# photocell_mk2.net
KiCad netlist of a schematic drawn in EAGLE
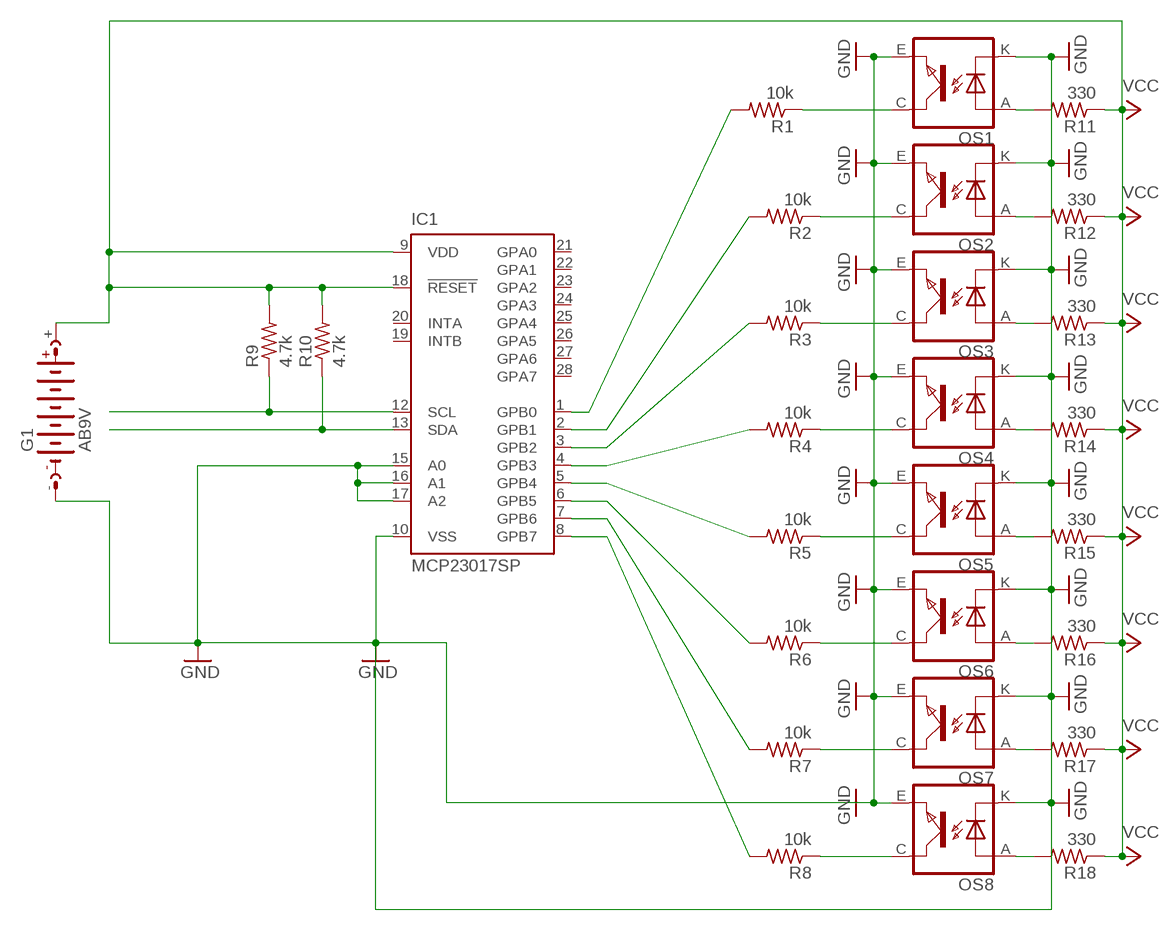
[diagram p0: schematic, sheet 1]

(export (version "E")
  (design (tool "Eeschema 10.0.6"))
  (components
    (comp (ref "G1")
      (value "AB9V")
      (footprint "eagle-import:AB9V")
      (libsource (lib "eagle-import") (part "AB9V"))
    )
    (comp (ref "IC1")
      (value "MCP23017SP")
      (footprint "eagle-import:DIL28-3")
      (fields (field (name "MF") "MICROCHIP") (field (name "MPN") "MCP23017-E/SP"))
      (libsource (lib "eagle-import") (part "MCP23017SP"))
    )
    (comp (ref "OS1")
      (value "TCRT5000")
      (footprint "eagle-import:TCRT5000")
      (libsource (lib "eagle-import") (part "TCRT5000"))
    )
    (comp (ref "OS2")
      (value "TCRT5000")
      (footprint "eagle-import:TCRT5000")
      (libsource (lib "eagle-import") (part "TCRT5000"))
    )
    (comp (ref "OS3")
      (value "TCRT5000")
      (footprint "eagle-import:TCRT5000")
      (libsource (lib "eagle-import") (part "TCRT5000"))
    )
    (comp (ref "OS4")
      (value "TCRT5000")
      (footprint "eagle-import:TCRT5000")
      (libsource (lib "eagle-import") (part "TCRT5000"))
    )
    (comp (ref "OS5")
      (value "TCRT5000")
      (footprint "eagle-import:TCRT5000")
      (libsource (lib "eagle-import") (part "TCRT5000"))
    )
    (comp (ref "OS6")
      (value "TCRT5000")
      (footprint "eagle-import:TCRT5000")
      (libsource (lib "eagle-import") (part "TCRT5000"))
    )
    (comp (ref "OS7")
      (value "TCRT5000")
      (footprint "eagle-import:TCRT5000")
      (libsource (lib "eagle-import") (part "TCRT5000"))
    )
    (comp (ref "OS8")
      (value "TCRT5000")
      (footprint "eagle-import:TCRT5000")
      (libsource (lib "eagle-import") (part "TCRT5000"))
    )
    (comp (ref "R1")
      (value "10k")
      (footprint "eagle-import:0204_7")
      (libsource (lib "eagle-import") (part "R-US_0204/7"))
    )
    (comp (ref "R2")
      (value "10k")
      (footprint "eagle-import:0204_7")
      (libsource (lib "eagle-import") (part "R-US_0204/7"))
    )
    (comp (ref "R3")
      (value "10k")
      (footprint "eagle-import:0204_7")
      (libsource (lib "eagle-import") (part "R-US_0204/7"))
    )
    (comp (ref "R4")
      (value "10k")
      (footprint "eagle-import:0204_7")
      (libsource (lib "eagle-import") (part "R-US_0204/7"))
    )
    (comp (ref "R5")
      (value "10k")
      (footprint "eagle-import:0204_7")
      (libsource (lib "eagle-import") (part "R-US_0204/7"))
    )
    (comp (ref "R6")
      (value "10k")
      (footprint "eagle-import:0204_7")
      (libsource (lib "eagle-import") (part "R-US_0204/7"))
    )
    (comp (ref "R7")
      (value "10k")
      (footprint "eagle-import:0204_7")
      (libsource (lib "eagle-import") (part "R-US_0204/7"))
    )
    (comp (ref "R8")
      (value "10k")
      (footprint "eagle-import:0204_7")
      (libsource (lib "eagle-import") (part "R-US_0204/7"))
    )
    (comp (ref "R9")
      (value "4.7k")
      (footprint "eagle-import:0204_7")
      (libsource (lib "eagle-import") (part "R-US_0204/7"))
    )
    (comp (ref "R10")
      (value "4.7k")
      (footprint "eagle-import:0204_7")
      (libsource (lib "eagle-import") (part "R-US_0204/7"))
    )
    (comp (ref "R11")
      (value "330")
      (footprint "eagle-import:0204_7")
      (libsource (lib "eagle-import") (part "R-US_0204/7"))
    )
    (comp (ref "R12")
      (value "330")
      (footprint "eagle-import:0204_7")
      (libsource (lib "eagle-import") (part "R-US_0204/7"))
    )
    (comp (ref "R13")
      (value "330")
      (footprint "eagle-import:0204_7")
      (libsource (lib "eagle-import") (part "R-US_0204/7"))
    )
    (comp (ref "R14")
      (value "330")
      (footprint "eagle-import:0204_7")
      (libsource (lib "eagle-import") (part "R-US_0204/7"))
    )
    (comp (ref "R15")
      (value "330")
      (footprint "eagle-import:0204_7")
      (libsource (lib "eagle-import") (part "R-US_0204/7"))
    )
    (comp (ref "R16")
      (value "330")
      (footprint "eagle-import:0204_7")
      (libsource (lib "eagle-import") (part "R-US_0204/7"))
    )
    (comp (ref "R17")
      (value "330")
      (footprint "eagle-import:0204_7")
      (libsource (lib "eagle-import") (part "R-US_0204/7"))
    )
    (comp (ref "R18")
      (value "330")
      (footprint "eagle-import:0204_7")
      (libsource (lib "eagle-import") (part "R-US_0204/7"))
    )
  )
  (nets
    (net (code "1") (name "GND") (class "Default")
      (node (ref "G1") (pin "-") (pinfunction "-_-") (pintype "passive"))
      (node (ref "IC1") (pin "10") (pinfunction "VSS_10") (pintype "power_in"))
      (node (ref "IC1") (pin "15") (pinfunction "A0_15") (pintype "input"))
      (node (ref "IC1") (pin "16") (pinfunction "A1_16") (pintype "input"))
      (node (ref "IC1") (pin "17") (pinfunction "A2_17") (pintype "input"))
      (node (ref "OS1") (pin "E") (pinfunction "EMITTER_E") (pintype "passive"))
      (node (ref "OS1") (pin "K") (pinfunction "CATHODE_K") (pintype "passive"))
      (node (ref "OS2") (pin "E") (pinfunction "EMITTER_E") (pintype "passive"))
      (node (ref "OS2") (pin "K") (pinfunction "CATHODE_K") (pintype "passive"))
      (node (ref "OS3") (pin "E") (pinfunction "EMITTER_E") (pintype "passive"))
      (node (ref "OS3") (pin "K") (pinfunction "CATHODE_K") (pintype "passive"))
      (node (ref "OS4") (pin "E") (pinfunction "EMITTER_E") (pintype "passive"))
      (node (ref "OS4") (pin "K") (pinfunction "CATHODE_K") (pintype "passive"))
      (node (ref "OS5") (pin "E") (pinfunction "EMITTER_E") (pintype "passive"))
      (node (ref "OS5") (pin "K") (pinfunction "CATHODE_K") (pintype "passive"))
      (node (ref "OS6") (pin "E") (pinfunction "EMITTER_E") (pintype "passive"))
      (node (ref "OS6") (pin "K") (pinfunction "CATHODE_K") (pintype "passive"))
      (node (ref "OS7") (pin "E") (pinfunction "EMITTER_E") (pintype "passive"))
      (node (ref "OS7") (pin "K") (pinfunction "CATHODE_K") (pintype "passive"))
      (node (ref "OS8") (pin "E") (pinfunction "EMITTER_E") (pintype "passive"))
      (node (ref "OS8") (pin "K") (pinfunction "CATHODE_K") (pintype "passive"))
    )
    (net (code "2") (name "Net-(IC1-GPB0)") (class "Default")
      (node (ref "IC1") (pin "1") (pinfunction "GPB0_1") (pintype "bidirectional"))
      (node (ref "R1") (pin "2") (pinfunction "2_2") (pintype "passive"))
    )
    (net (code "3") (name "Net-(IC1-GPB1)") (class "Default")
      (node (ref "IC1") (pin "2") (pinfunction "GPB1_2") (pintype "bidirectional"))
      (node (ref "R2") (pin "2") (pinfunction "2_2") (pintype "passive"))
    )
    (net (code "4") (name "Net-(IC1-GPB2)") (class "Default")
      (node (ref "IC1") (pin "3") (pinfunction "GPB2_3") (pintype "bidirectional"))
      (node (ref "R3") (pin "2") (pinfunction "2_2") (pintype "passive"))
    )
    (net (code "5") (name "Net-(IC1-GPB3)") (class "Default")
      (node (ref "IC1") (pin "4") (pinfunction "GPB3_4") (pintype "bidirectional"))
      (node (ref "R4") (pin "2") (pinfunction "2_2") (pintype "passive"))
    )
    (net (code "6") (name "Net-(IC1-GPB4)") (class "Default")
      (node (ref "IC1") (pin "5") (pinfunction "GPB4_5") (pintype "bidirectional"))
      (node (ref "R5") (pin "2") (pinfunction "2_2") (pintype "passive"))
    )
    (net (code "7") (name "Net-(IC1-GPB5)") (class "Default")
      (node (ref "IC1") (pin "6") (pinfunction "GPB5_6") (pintype "bidirectional"))
      (node (ref "R6") (pin "2") (pinfunction "2_2") (pintype "passive"))
    )
    (net (code "8") (name "Net-(IC1-GPB6)") (class "Default")
      (node (ref "IC1") (pin "7") (pinfunction "GPB6_7") (pintype "bidirectional"))
      (node (ref "R7") (pin "2") (pinfunction "2_2") (pintype "passive"))
    )
    (net (code "9") (name "Net-(IC1-GPB7)") (class "Default")
      (node (ref "IC1") (pin "8") (pinfunction "GPB7_8") (pintype "bidirectional"))
      (node (ref "R8") (pin "2") (pinfunction "2_2") (pintype "passive"))
    )
    (net (code "10") (name "Net-(IC1-SCL)") (class "Default")
      (node (ref "IC1") (pin "12") (pinfunction "SCL_12") (pintype "input"))
      (node (ref "R9") (pin "1") (pinfunction "1_1") (pintype "passive"))
    )
    (net (code "11") (name "Net-(IC1-SDA)") (class "Default")
      (node (ref "IC1") (pin "13") (pinfunction "SDA_13") (pintype "bidirectional"))
      (node (ref "R10") (pin "1") (pinfunction "1_1") (pintype "passive"))
    )
    (net (code "12") (name "Net-(OS1-ANODE)") (class "Default")
      (node (ref "OS1") (pin "A") (pinfunction "ANODE_A") (pintype "passive"))
      (node (ref "R11") (pin "2") (pinfunction "2_2") (pintype "passive"))
    )
    (net (code "13") (name "Net-(OS1-COLLECTOR)") (class "Default")
      (node (ref "OS1") (pin "C") (pinfunction "COLLECTOR_C") (pintype "passive"))
      (node (ref "R1") (pin "1") (pinfunction "1_1") (pintype "passive"))
    )
    (net (code "14") (name "Net-(OS2-ANODE)") (class "Default")
      (node (ref "OS2") (pin "A") (pinfunction "ANODE_A") (pintype "passive"))
      (node (ref "R12") (pin "2") (pinfunction "2_2") (pintype "passive"))
    )
    (net (code "15") (name "Net-(OS2-COLLECTOR)") (class "Default")
      (node (ref "OS2") (pin "C") (pinfunction "COLLECTOR_C") (pintype "passive"))
      (node (ref "R2") (pin "1") (pinfunction "1_1") (pintype "passive"))
    )
    (net (code "16") (name "Net-(OS3-ANODE)") (class "Default")
      (node (ref "OS3") (pin "A") (pinfunction "ANODE_A") (pintype "passive"))
      (node (ref "R13") (pin "2") (pinfunction "2_2") (pintype "passive"))
    )
    (net (code "17") (name "Net-(OS3-COLLECTOR)") (class "Default")
      (node (ref "OS3") (pin "C") (pinfunction "COLLECTOR_C") (pintype "passive"))
      (node (ref "R3") (pin "1") (pinfunction "1_1") (pintype "passive"))
    )
    (net (code "18") (name "Net-(OS4-ANODE)") (class "Default")
      (node (ref "OS4") (pin "A") (pinfunction "ANODE_A") (pintype "passive"))
      (node (ref "R14") (pin "2") (pinfunction "2_2") (pintype "passive"))
    )
    (net (code "19") (name "Net-(OS4-COLLECTOR)") (class "Default")
      (node (ref "OS4") (pin "C") (pinfunction "COLLECTOR_C") (pintype "passive"))
      (node (ref "R4") (pin "1") (pinfunction "1_1") (pintype "passive"))
    )
    (net (code "20") (name "Net-(OS5-ANODE)") (class "Default")
      (node (ref "OS5") (pin "A") (pinfunction "ANODE_A") (pintype "passive"))
      (node (ref "R15") (pin "2") (pinfunction "2_2") (pintype "passive"))
    )
    (net (code "21") (name "Net-(OS5-COLLECTOR)") (class "Default")
      (node (ref "OS5") (pin "C") (pinfunction "COLLECTOR_C") (pintype "passive"))
      (node (ref "R5") (pin "1") (pinfunction "1_1") (pintype "passive"))
    )
    (net (code "22") (name "Net-(OS6-ANODE)") (class "Default")
      (node (ref "OS6") (pin "A") (pinfunction "ANODE_A") (pintype "passive"))
      (node (ref "R16") (pin "2") (pinfunction "2_2") (pintype "passive"))
    )
    (net (code "23") (name "Net-(OS6-COLLECTOR)") (class "Default")
      (node (ref "OS6") (pin "C") (pinfunction "COLLECTOR_C") (pintype "passive"))
      (node (ref "R6") (pin "1") (pinfunction "1_1") (pintype "passive"))
    )
    (net (code "24") (name "Net-(OS7-ANODE)") (class "Default")
      (node (ref "OS7") (pin "A") (pinfunction "ANODE_A") (pintype "passive"))
      (node (ref "R17") (pin "2") (pinfunction "2_2") (pintype "passive"))
    )
    (net (code "25") (name "Net-(OS7-COLLECTOR)") (class "Default")
      (node (ref "OS7") (pin "C") (pinfunction "COLLECTOR_C") (pintype "passive"))
      (node (ref "R7") (pin "1") (pinfunction "1_1") (pintype "passive"))
    )
    (net (code "26") (name "Net-(OS8-ANODE)") (class "Default")
      (node (ref "OS8") (pin "A") (pinfunction "ANODE_A") (pintype "passive"))
      (node (ref "R18") (pin "2") (pinfunction "2_2") (pintype "passive"))
    )
    (net (code "27") (name "Net-(OS8-COLLECTOR)") (class "Default")
      (node (ref "OS8") (pin "C") (pinfunction "COLLECTOR_C") (pintype "passive"))
      (node (ref "R8") (pin "1") (pinfunction "1_1") (pintype "passive"))
    )
    (net (code "28") (name "VCC") (class "Default")
      (node (ref "G1") (pin "+") (pinfunction "+_+") (pintype "passive"))
      (node (ref "IC1") (pin "18") (pinfunction "~{RESET}_18") (pintype "input"))
      (node (ref "IC1") (pin "9") (pinfunction "VDD_9") (pintype "power_in"))
      (node (ref "R10") (pin "2") (pinfunction "2_2") (pintype "passive"))
      (node (ref "R11") (pin "1") (pinfunction "1_1") (pintype "passive"))
      (node (ref "R12") (pin "1") (pinfunction "1_1") (pintype "passive"))
      (node (ref "R13") (pin "1") (pinfunction "1_1") (pintype "passive"))
      (node (ref "R14") (pin "1") (pinfunction "1_1") (pintype "passive"))
      (node (ref "R15") (pin "1") (pinfunction "1_1") (pintype "passive"))
      (node (ref "R16") (pin "1") (pinfunction "1_1") (pintype "passive"))
      (node (ref "R17") (pin "1") (pinfunction "1_1") (pintype "passive"))
      (node (ref "R18") (pin "1") (pinfunction "1_1") (pintype "passive"))
      (node (ref "R9") (pin "2") (pinfunction "2_2") (pintype "passive"))
    )
    (net (code "29") (name "unconnected-(IC1-GPA0-Pad21)") (class "Default")
      (node (ref "IC1") (pin "21") (pinfunction "GPA0_21") (pintype "bidirectional"))
    )
    (net (code "30") (name "unconnected-(IC1-GPA1-Pad22)") (class "Default")
      (node (ref "IC1") (pin "22") (pinfunction "GPA1_22") (pintype "bidirectional"))
    )
    (net (code "31") (name "unconnected-(IC1-GPA2-Pad23)") (class "Default")
      (node (ref "IC1") (pin "23") (pinfunction "GPA2_23") (pintype "bidirectional"))
    )
    (net (code "32") (name "unconnected-(IC1-GPA3-Pad24)") (class "Default")
      (node (ref "IC1") (pin "24") (pinfunction "GPA3_24") (pintype "bidirectional"))
    )
    (net (code "33") (name "unconnected-(IC1-GPA4-Pad25)") (class "Default")
      (node (ref "IC1") (pin "25") (pinfunction "GPA4_25") (pintype "bidirectional"))
    )
    (net (code "34") (name "unconnected-(IC1-GPA5-Pad26)") (class "Default")
      (node (ref "IC1") (pin "26") (pinfunction "GPA5_26") (pintype "bidirectional"))
    )
    (net (code "35") (name "unconnected-(IC1-GPA6-Pad27)") (class "Default")
      (node (ref "IC1") (pin "27") (pinfunction "GPA6_27") (pintype "bidirectional"))
    )
    (net (code "36") (name "unconnected-(IC1-GPA7-Pad28)") (class "Default")
      (node (ref "IC1") (pin "28") (pinfunction "GPA7_28") (pintype "bidirectional"))
    )
    (net (code "37") (name "unconnected-(IC1-INTA-Pad20)") (class "Default")
      (node (ref "IC1") (pin "20") (pinfunction "INTA_20") (pintype "output"))
    )
    (net (code "38") (name "unconnected-(IC1-INTB-Pad19)") (class "Default")
      (node (ref "IC1") (pin "19") (pinfunction "INTB_19") (pintype "output"))
    )
  )
)
